# riffle-turbidity.net
KiCad netlist of a schematic drawn in EAGLE
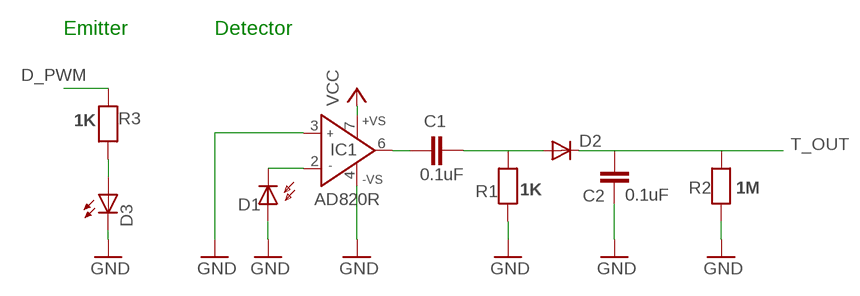
[diagram p0: schematic, sheet 1]

(export (version "E")
  (design (tool "Eeschema 10.0.6"))
  (components
    (comp (ref "C1")
      (value "0.1uF")
      (footprint "eagle-import:0603-CAP")
      (libsource (lib "eagle-import") (part "CAP0603-CAP"))
    )
    (comp (ref "C2")
      (value "0.1uF")
      (footprint "eagle-import:0603-CAP")
      (libsource (lib "eagle-import") (part "CAP0603-CAP"))
    )
    (comp (ref "D1")
      (value "BPX65")
      (footprint "eagle-import:BPX65")
      (fields (field (name "MPN") "BPX65."))
      (libsource (lib "eagle-import") (part "BPX65"))
    )
    (comp (ref "D2")
      (value "1N4148DO35-7")
      (footprint "eagle-import:DO35-7")
      (libsource (lib "eagle-import") (part "1N4148DO35-7"))
    )
    (comp (ref "D3")
      (value "LZ1-00WW03")
      (footprint "eagle-import:LZ1-00WW03")
      (libsource (lib "eagle-import") (part "LZ1-00WW03"))
    )
    (comp (ref "IC1")
      (value "AD820R")
      (footprint "eagle-import:SO8")
      (libsource (lib "eagle-import") (part "AD820R"))
    )
    (comp (ref "R1")
      (value "1K")
      (footprint "eagle-import:0603-NO")
      (libsource (lib "eagle-import") (part "RESISTOR_0603_NOOUT"))
    )
    (comp (ref "R2")
      (value "1M")
      (footprint "eagle-import:0603-NO")
      (libsource (lib "eagle-import") (part "RESISTOR_0603_NOOUT"))
    )
    (comp (ref "R3")
      (value "1K")
      (footprint "eagle-import:0603-NO")
      (libsource (lib "eagle-import") (part "RESISTOR_0603_NOOUT"))
    )
  )
  (nets
    (net (code "1") (name "/D_PWM") (class "Default")
      (node (ref "R3") (pin "1") (pinfunction "1_1") (pintype "passive"))
    )
    (net (code "2") (name "/T_OUT") (class "Default")
      (node (ref "C2") (pin "2") (pinfunction "2_2") (pintype "passive"))
      (node (ref "D2") (pin "C") (pinfunction "C_C") (pintype "passive"))
      (node (ref "R2") (pin "2") (pinfunction "2_2") (pintype "passive"))
    )
    (net (code "3") (name "GND") (class "Default")
      (node (ref "C2") (pin "1") (pinfunction "1_1") (pintype "passive"))
      (node (ref "D1") (pin "A") (pinfunction "A_A") (pintype "passive"))
      (node (ref "D3") (pin "1") (pinfunction "C_1") (pintype "passive"))
      (node (ref "D3") (pin "4") (pinfunction "C_4") (pintype "passive"))
      (node (ref "IC1") (pin "3") (pinfunction "IN+_3") (pintype "input"))
      (node (ref "IC1") (pin "4") (pinfunction "-VS_4") (pintype "input"))
      (node (ref "R1") (pin "1") (pinfunction "1_1") (pintype "passive"))
      (node (ref "R2") (pin "1") (pinfunction "1_1") (pintype "passive"))
    )
    (net (code "4") (name "Net-(C1-Pad1)") (class "Default")
      (node (ref "C1") (pin "1") (pinfunction "1_1") (pintype "passive"))
      (node (ref "D2") (pin "A") (pinfunction "A_A") (pintype "passive"))
      (node (ref "R1") (pin "2") (pinfunction "2_2") (pintype "passive"))
    )
    (net (code "5") (name "Net-(D1-C)") (class "Default")
      (node (ref "D1") (pin "K") (pinfunction "C_K") (pintype "passive"))
      (node (ref "IC1") (pin "2") (pinfunction "IN-_2") (pintype "input"))
    )
    (net (code "6") (name "Net-(D3-A-Pad2)") (class "Default")
      (node (ref "D3") (pin "2") (pinfunction "A_2") (pintype "passive"))
      (node (ref "D3") (pin "3") (pinfunction "A_3") (pintype "passive"))
      (node (ref "D3") (pin "5") (pinfunction "A_5") (pintype "passive"))
      (node (ref "R3") (pin "2") (pinfunction "2_2") (pintype "passive"))
    )
    (net (code "7") (name "Net-(IC1-OUT)") (class "Default")
      (node (ref "C1") (pin "2") (pinfunction "2_2") (pintype "passive"))
      (node (ref "IC1") (pin "6") (pinfunction "OUT_6") (pintype "output"))
    )
    (net (code "8") (name "VCC") (class "Default")
      (node (ref "IC1") (pin "7") (pinfunction "+VS_7") (pintype "input"))
    )
  )
)
